# shift-register.net
KiCad netlist of a schematic drawn in EAGLE
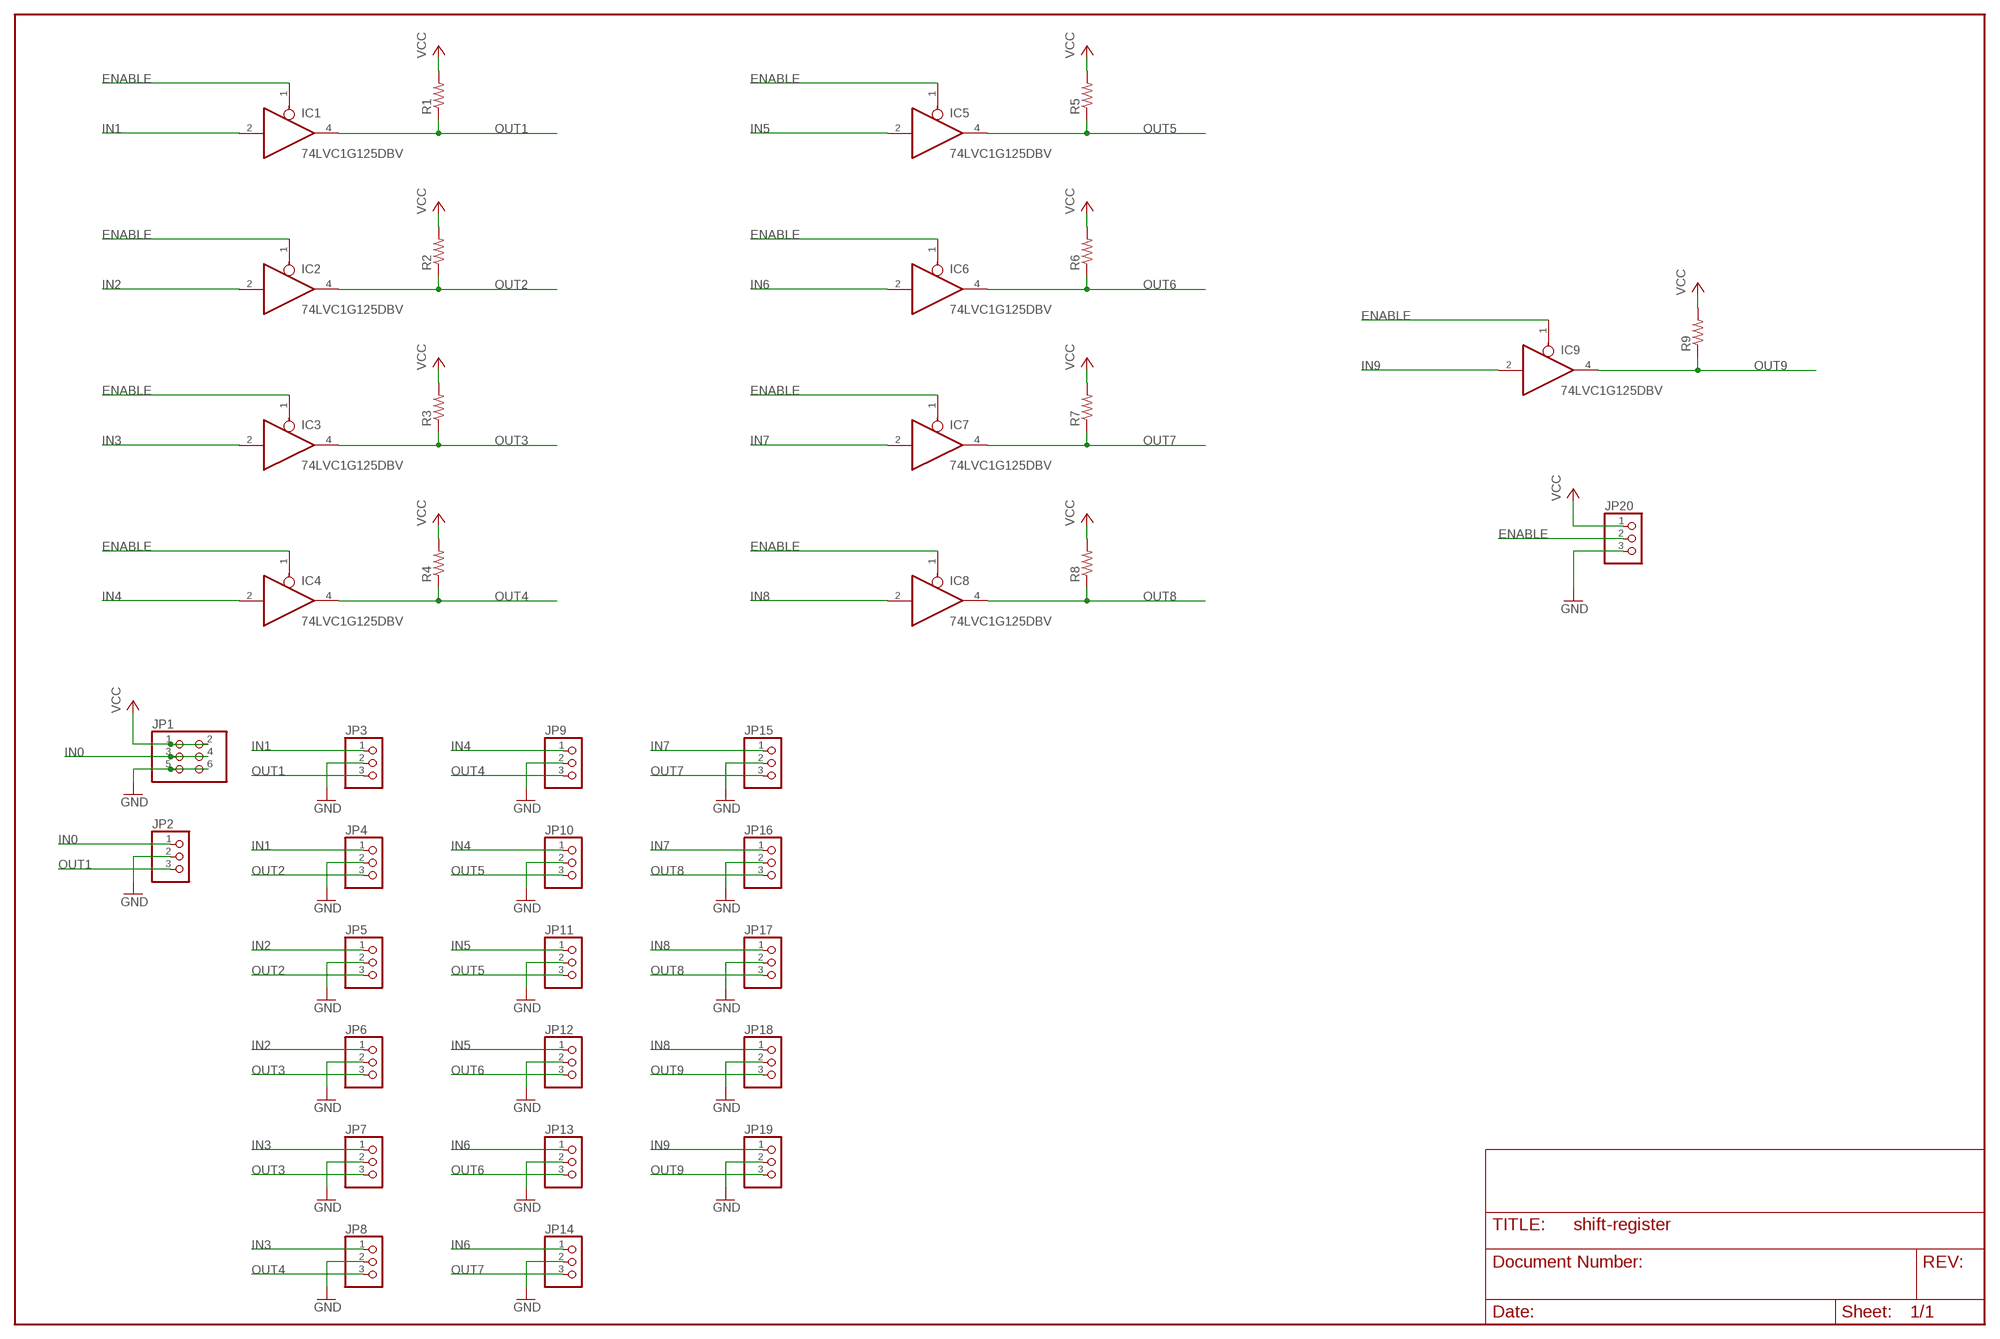
[diagram p0: schematic, sheet 1]

(export (version "E")
  (design (tool "Eeschema 10.0.6"))
  (components
    (comp (ref "IC1")
      (value "74LVC1G125DBV")
      (footprint "eagle-import:SOT23-5")
      (libsource (lib "eagle-import") (part "741G125DBVLVC"))
    )
    (comp (ref "IC2")
      (value "74LVC1G125DBV")
      (footprint "eagle-import:SOT23-5")
      (libsource (lib "eagle-import") (part "741G125DBVLVC"))
    )
    (comp (ref "IC3")
      (value "74LVC1G125DBV")
      (footprint "eagle-import:SOT23-5")
      (libsource (lib "eagle-import") (part "741G125DBVLVC"))
    )
    (comp (ref "IC4")
      (value "74LVC1G125DBV")
      (footprint "eagle-import:SOT23-5")
      (libsource (lib "eagle-import") (part "741G125DBVLVC"))
    )
    (comp (ref "IC5")
      (value "74LVC1G125DBV")
      (footprint "eagle-import:SOT23-5")
      (libsource (lib "eagle-import") (part "741G125DBVLVC"))
    )
    (comp (ref "IC6")
      (value "74LVC1G125DBV")
      (footprint "eagle-import:SOT23-5")
      (libsource (lib "eagle-import") (part "741G125DBVLVC"))
    )
    (comp (ref "IC7")
      (value "74LVC1G125DBV")
      (footprint "eagle-import:SOT23-5")
      (libsource (lib "eagle-import") (part "741G125DBVLVC"))
    )
    (comp (ref "IC8")
      (value "74LVC1G125DBV")
      (footprint "eagle-import:SOT23-5")
      (libsource (lib "eagle-import") (part "741G125DBVLVC"))
    )
    (comp (ref "IC9")
      (value "74LVC1G125DBV")
      (footprint "eagle-import:SOT23-5")
      (libsource (lib "eagle-import") (part "741G125DBVLVC"))
    )
    (comp (ref "JP1")
      (value "PINHD-2X3")
      (footprint "eagle-import:2X03")
      (libsource (lib "eagle-import") (part "PINHD-2X3"))
    )
    (comp (ref "JP2")
      (value "PINHD-1X3")
      (footprint "eagle-import:1X03")
      (libsource (lib "eagle-import") (part "PINHD-1X3"))
    )
    (comp (ref "JP3")
      (value "PINHD-1X3")
      (footprint "eagle-import:1X03")
      (libsource (lib "eagle-import") (part "PINHD-1X3"))
    )
    (comp (ref "JP4")
      (value "PINHD-1X3")
      (footprint "eagle-import:1X03")
      (libsource (lib "eagle-import") (part "PINHD-1X3"))
    )
    (comp (ref "JP5")
      (value "PINHD-1X3")
      (footprint "eagle-import:1X03")
      (libsource (lib "eagle-import") (part "PINHD-1X3"))
    )
    (comp (ref "JP6")
      (value "PINHD-1X3")
      (footprint "eagle-import:1X03")
      (libsource (lib "eagle-import") (part "PINHD-1X3"))
    )
    (comp (ref "JP7")
      (value "PINHD-1X3")
      (footprint "eagle-import:1X03")
      (libsource (lib "eagle-import") (part "PINHD-1X3"))
    )
    (comp (ref "JP8")
      (value "PINHD-1X3")
      (footprint "eagle-import:1X03")
      (libsource (lib "eagle-import") (part "PINHD-1X3"))
    )
    (comp (ref "JP9")
      (value "PINHD-1X3")
      (footprint "eagle-import:1X03")
      (libsource (lib "eagle-import") (part "PINHD-1X3"))
    )
    (comp (ref "JP10")
      (value "PINHD-1X3")
      (footprint "eagle-import:1X03")
      (libsource (lib "eagle-import") (part "PINHD-1X3"))
    )
    (comp (ref "JP11")
      (value "PINHD-1X3")
      (footprint "eagle-import:1X03")
      (libsource (lib "eagle-import") (part "PINHD-1X3"))
    )
    (comp (ref "JP12")
      (value "PINHD-1X3")
      (footprint "eagle-import:1X03")
      (libsource (lib "eagle-import") (part "PINHD-1X3"))
    )
    (comp (ref "JP13")
      (value "PINHD-1X3")
      (footprint "eagle-import:1X03")
      (libsource (lib "eagle-import") (part "PINHD-1X3"))
    )
    (comp (ref "JP14")
      (value "PINHD-1X3")
      (footprint "eagle-import:1X03")
      (libsource (lib "eagle-import") (part "PINHD-1X3"))
    )
    (comp (ref "JP15")
      (value "PINHD-1X3")
      (footprint "eagle-import:1X03")
      (libsource (lib "eagle-import") (part "PINHD-1X3"))
    )
    (comp (ref "JP16")
      (value "PINHD-1X3")
      (footprint "eagle-import:1X03")
      (libsource (lib "eagle-import") (part "PINHD-1X3"))
    )
    (comp (ref "JP17")
      (value "PINHD-1X3")
      (footprint "eagle-import:1X03")
      (libsource (lib "eagle-import") (part "PINHD-1X3"))
    )
    (comp (ref "JP18")
      (value "PINHD-1X3")
      (footprint "eagle-import:1X03")
      (libsource (lib "eagle-import") (part "PINHD-1X3"))
    )
    (comp (ref "JP19")
      (value "PINHD-1X3")
      (footprint "eagle-import:1X03")
      (libsource (lib "eagle-import") (part "PINHD-1X3"))
    )
    (comp (ref "JP20")
      (value "PINHD-1X3")
      (footprint "eagle-import:1X03")
      (libsource (lib "eagle-import") (part "PINHD-1X3"))
    )
    (comp (ref "R1")
      (value "R-US_R0603")
      (footprint "eagle-import:R0603")
      (libsource (lib "eagle-import") (part "R-US_R0603"))
    )
    (comp (ref "R2")
      (value "R-US_R0603")
      (footprint "eagle-import:R0603")
      (libsource (lib "eagle-import") (part "R-US_R0603"))
    )
    (comp (ref "R3")
      (value "R-US_R0603")
      (footprint "eagle-import:R0603")
      (libsource (lib "eagle-import") (part "R-US_R0603"))
    )
    (comp (ref "R4")
      (value "R-US_R0603")
      (footprint "eagle-import:R0603")
      (libsource (lib "eagle-import") (part "R-US_R0603"))
    )
    (comp (ref "R5")
      (value "R-US_R0603")
      (footprint "eagle-import:R0603")
      (libsource (lib "eagle-import") (part "R-US_R0603"))
    )
    (comp (ref "R6")
      (value "R-US_R0603")
      (footprint "eagle-import:R0603")
      (libsource (lib "eagle-import") (part "R-US_R0603"))
    )
    (comp (ref "R7")
      (value "R-US_R0603")
      (footprint "eagle-import:R0603")
      (libsource (lib "eagle-import") (part "R-US_R0603"))
    )
    (comp (ref "R8")
      (value "R-US_R0603")
      (footprint "eagle-import:R0603")
      (libsource (lib "eagle-import") (part "R-US_R0603"))
    )
    (comp (ref "R9")
      (value "R-US_R0603")
      (footprint "eagle-import:R0603")
      (libsource (lib "eagle-import") (part "R-US_R0603"))
    )
  )
  (nets
    (net (code "1") (name "/ENABLE") (class "Default")
      (node (ref "IC1") (pin "1") (pinfunction "OE_1") (pintype "input"))
      (node (ref "IC2") (pin "1") (pinfunction "OE_1") (pintype "input"))
      (node (ref "IC3") (pin "1") (pinfunction "OE_1") (pintype "input"))
      (node (ref "IC4") (pin "1") (pinfunction "OE_1") (pintype "input"))
      (node (ref "IC5") (pin "1") (pinfunction "OE_1") (pintype "input"))
      (node (ref "IC6") (pin "1") (pinfunction "OE_1") (pintype "input"))
      (node (ref "IC7") (pin "1") (pinfunction "OE_1") (pintype "input"))
      (node (ref "IC8") (pin "1") (pinfunction "OE_1") (pintype "input"))
      (node (ref "IC9") (pin "1") (pinfunction "OE_1") (pintype "input"))
      (node (ref "JP20") (pin "2") (pinfunction "2_2") (pintype "passive"))
    )
    (net (code "2") (name "/IN0") (class "Default")
      (node (ref "JP1") (pin "3") (pinfunction "3_3") (pintype "passive"))
      (node (ref "JP1") (pin "4") (pinfunction "4_4") (pintype "passive"))
      (node (ref "JP2") (pin "1") (pinfunction "1_1") (pintype "passive"))
    )
    (net (code "3") (name "/IN1") (class "Default")
      (node (ref "IC1") (pin "2") (pinfunction "I_2") (pintype "input"))
      (node (ref "JP3") (pin "1") (pinfunction "1_1") (pintype "passive"))
      (node (ref "JP4") (pin "1") (pinfunction "1_1") (pintype "passive"))
    )
    (net (code "4") (name "/IN2") (class "Default")
      (node (ref "IC2") (pin "2") (pinfunction "I_2") (pintype "input"))
      (node (ref "JP5") (pin "1") (pinfunction "1_1") (pintype "passive"))
      (node (ref "JP6") (pin "1") (pinfunction "1_1") (pintype "passive"))
    )
    (net (code "5") (name "/IN3") (class "Default")
      (node (ref "IC3") (pin "2") (pinfunction "I_2") (pintype "input"))
      (node (ref "JP7") (pin "1") (pinfunction "1_1") (pintype "passive"))
      (node (ref "JP8") (pin "1") (pinfunction "1_1") (pintype "passive"))
    )
    (net (code "6") (name "/IN4") (class "Default")
      (node (ref "IC4") (pin "2") (pinfunction "I_2") (pintype "input"))
      (node (ref "JP10") (pin "1") (pinfunction "1_1") (pintype "passive"))
      (node (ref "JP9") (pin "1") (pinfunction "1_1") (pintype "passive"))
    )
    (net (code "7") (name "/IN5") (class "Default")
      (node (ref "IC5") (pin "2") (pinfunction "I_2") (pintype "input"))
      (node (ref "JP11") (pin "1") (pinfunction "1_1") (pintype "passive"))
      (node (ref "JP12") (pin "1") (pinfunction "1_1") (pintype "passive"))
    )
    (net (code "8") (name "/IN6") (class "Default")
      (node (ref "IC6") (pin "2") (pinfunction "I_2") (pintype "input"))
      (node (ref "JP13") (pin "1") (pinfunction "1_1") (pintype "passive"))
      (node (ref "JP14") (pin "1") (pinfunction "1_1") (pintype "passive"))
    )
    (net (code "9") (name "/IN7") (class "Default")
      (node (ref "IC7") (pin "2") (pinfunction "I_2") (pintype "input"))
      (node (ref "JP15") (pin "1") (pinfunction "1_1") (pintype "passive"))
      (node (ref "JP16") (pin "1") (pinfunction "1_1") (pintype "passive"))
    )
    (net (code "10") (name "/IN8") (class "Default")
      (node (ref "IC8") (pin "2") (pinfunction "I_2") (pintype "input"))
      (node (ref "JP17") (pin "1") (pinfunction "1_1") (pintype "passive"))
      (node (ref "JP18") (pin "1") (pinfunction "1_1") (pintype "passive"))
    )
    (net (code "11") (name "/IN9") (class "Default")
      (node (ref "IC9") (pin "2") (pinfunction "I_2") (pintype "input"))
      (node (ref "JP19") (pin "1") (pinfunction "1_1") (pintype "passive"))
    )
    (net (code "12") (name "/OUT1") (class "Default")
      (node (ref "IC1") (pin "4") (pinfunction "O_4") (pintype "tri_state"))
      (node (ref "JP2") (pin "3") (pinfunction "3_3") (pintype "passive"))
      (node (ref "JP3") (pin "3") (pinfunction "3_3") (pintype "passive"))
      (node (ref "R1") (pin "1") (pinfunction "1_1") (pintype "passive"))
    )
    (net (code "13") (name "/OUT2") (class "Default")
      (node (ref "IC2") (pin "4") (pinfunction "O_4") (pintype "tri_state"))
      (node (ref "JP4") (pin "3") (pinfunction "3_3") (pintype "passive"))
      (node (ref "JP5") (pin "3") (pinfunction "3_3") (pintype "passive"))
      (node (ref "R2") (pin "1") (pinfunction "1_1") (pintype "passive"))
    )
    (net (code "14") (name "/OUT3") (class "Default")
      (node (ref "IC3") (pin "4") (pinfunction "O_4") (pintype "tri_state"))
      (node (ref "JP6") (pin "3") (pinfunction "3_3") (pintype "passive"))
      (node (ref "JP7") (pin "3") (pinfunction "3_3") (pintype "passive"))
      (node (ref "R3") (pin "1") (pinfunction "1_1") (pintype "passive"))
    )
    (net (code "15") (name "/OUT4") (class "Default")
      (node (ref "IC4") (pin "4") (pinfunction "O_4") (pintype "tri_state"))
      (node (ref "JP8") (pin "3") (pinfunction "3_3") (pintype "passive"))
      (node (ref "JP9") (pin "3") (pinfunction "3_3") (pintype "passive"))
      (node (ref "R4") (pin "1") (pinfunction "1_1") (pintype "passive"))
    )
    (net (code "16") (name "/OUT5") (class "Default")
      (node (ref "IC5") (pin "4") (pinfunction "O_4") (pintype "tri_state"))
      (node (ref "JP10") (pin "3") (pinfunction "3_3") (pintype "passive"))
      (node (ref "JP11") (pin "3") (pinfunction "3_3") (pintype "passive"))
      (node (ref "R5") (pin "1") (pinfunction "1_1") (pintype "passive"))
    )
    (net (code "17") (name "/OUT6") (class "Default")
      (node (ref "IC6") (pin "4") (pinfunction "O_4") (pintype "tri_state"))
      (node (ref "JP12") (pin "3") (pinfunction "3_3") (pintype "passive"))
      (node (ref "JP13") (pin "3") (pinfunction "3_3") (pintype "passive"))
      (node (ref "R6") (pin "1") (pinfunction "1_1") (pintype "passive"))
    )
    (net (code "18") (name "/OUT7") (class "Default")
      (node (ref "IC7") (pin "4") (pinfunction "O_4") (pintype "tri_state"))
      (node (ref "JP14") (pin "3") (pinfunction "3_3") (pintype "passive"))
      (node (ref "JP15") (pin "3") (pinfunction "3_3") (pintype "passive"))
      (node (ref "R7") (pin "1") (pinfunction "1_1") (pintype "passive"))
    )
    (net (code "19") (name "/OUT8") (class "Default")
      (node (ref "IC8") (pin "4") (pinfunction "O_4") (pintype "tri_state"))
      (node (ref "JP16") (pin "3") (pinfunction "3_3") (pintype "passive"))
      (node (ref "JP17") (pin "3") (pinfunction "3_3") (pintype "passive"))
      (node (ref "R8") (pin "1") (pinfunction "1_1") (pintype "passive"))
    )
    (net (code "20") (name "/OUT9") (class "Default")
      (node (ref "IC9") (pin "4") (pinfunction "O_4") (pintype "tri_state"))
      (node (ref "JP18") (pin "3") (pinfunction "3_3") (pintype "passive"))
      (node (ref "JP19") (pin "3") (pinfunction "3_3") (pintype "passive"))
      (node (ref "R9") (pin "1") (pinfunction "1_1") (pintype "passive"))
    )
    (net (code "21") (name "GND") (class "Default")
      (node (ref "JP1") (pin "5") (pinfunction "5_5") (pintype "passive"))
      (node (ref "JP1") (pin "6") (pinfunction "6_6") (pintype "passive"))
      (node (ref "JP10") (pin "2") (pinfunction "2_2") (pintype "passive"))
      (node (ref "JP11") (pin "2") (pinfunction "2_2") (pintype "passive"))
      (node (ref "JP12") (pin "2") (pinfunction "2_2") (pintype "passive"))
      (node (ref "JP13") (pin "2") (pinfunction "2_2") (pintype "passive"))
      (node (ref "JP14") (pin "2") (pinfunction "2_2") (pintype "passive"))
      (node (ref "JP15") (pin "2") (pinfunction "2_2") (pintype "passive"))
      (node (ref "JP16") (pin "2") (pinfunction "2_2") (pintype "passive"))
      (node (ref "JP17") (pin "2") (pinfunction "2_2") (pintype "passive"))
      (node (ref "JP18") (pin "2") (pinfunction "2_2") (pintype "passive"))
      (node (ref "JP19") (pin "2") (pinfunction "2_2") (pintype "passive"))
      (node (ref "JP2") (pin "2") (pinfunction "2_2") (pintype "passive"))
      (node (ref "JP20") (pin "3") (pinfunction "3_3") (pintype "passive"))
      (node (ref "JP3") (pin "2") (pinfunction "2_2") (pintype "passive"))
      (node (ref "JP4") (pin "2") (pinfunction "2_2") (pintype "passive"))
      (node (ref "JP5") (pin "2") (pinfunction "2_2") (pintype "passive"))
      (node (ref "JP6") (pin "2") (pinfunction "2_2") (pintype "passive"))
      (node (ref "JP7") (pin "2") (pinfunction "2_2") (pintype "passive"))
      (node (ref "JP8") (pin "2") (pinfunction "2_2") (pintype "passive"))
      (node (ref "JP9") (pin "2") (pinfunction "2_2") (pintype "passive"))
    )
    (net (code "22") (name "VCC") (class "Default")
      (node (ref "JP1") (pin "1") (pinfunction "1_1") (pintype "passive"))
      (node (ref "JP1") (pin "2") (pinfunction "2_2") (pintype "passive"))
      (node (ref "JP20") (pin "1") (pinfunction "1_1") (pintype "passive"))
      (node (ref "R1") (pin "2") (pinfunction "2_2") (pintype "passive"))
      (node (ref "R2") (pin "2") (pinfunction "2_2") (pintype "passive"))
      (node (ref "R3") (pin "2") (pinfunction "2_2") (pintype "passive"))
      (node (ref "R4") (pin "2") (pinfunction "2_2") (pintype "passive"))
      (node (ref "R5") (pin "2") (pinfunction "2_2") (pintype "passive"))
      (node (ref "R6") (pin "2") (pinfunction "2_2") (pintype "passive"))
      (node (ref "R7") (pin "2") (pinfunction "2_2") (pintype "passive"))
      (node (ref "R8") (pin "2") (pinfunction "2_2") (pintype "passive"))
      (node (ref "R9") (pin "2") (pinfunction "2_2") (pintype "passive"))
    )
  )
)
